# precharge_relays.net
KiCad netlist of a schematic drawn in Altium Designer
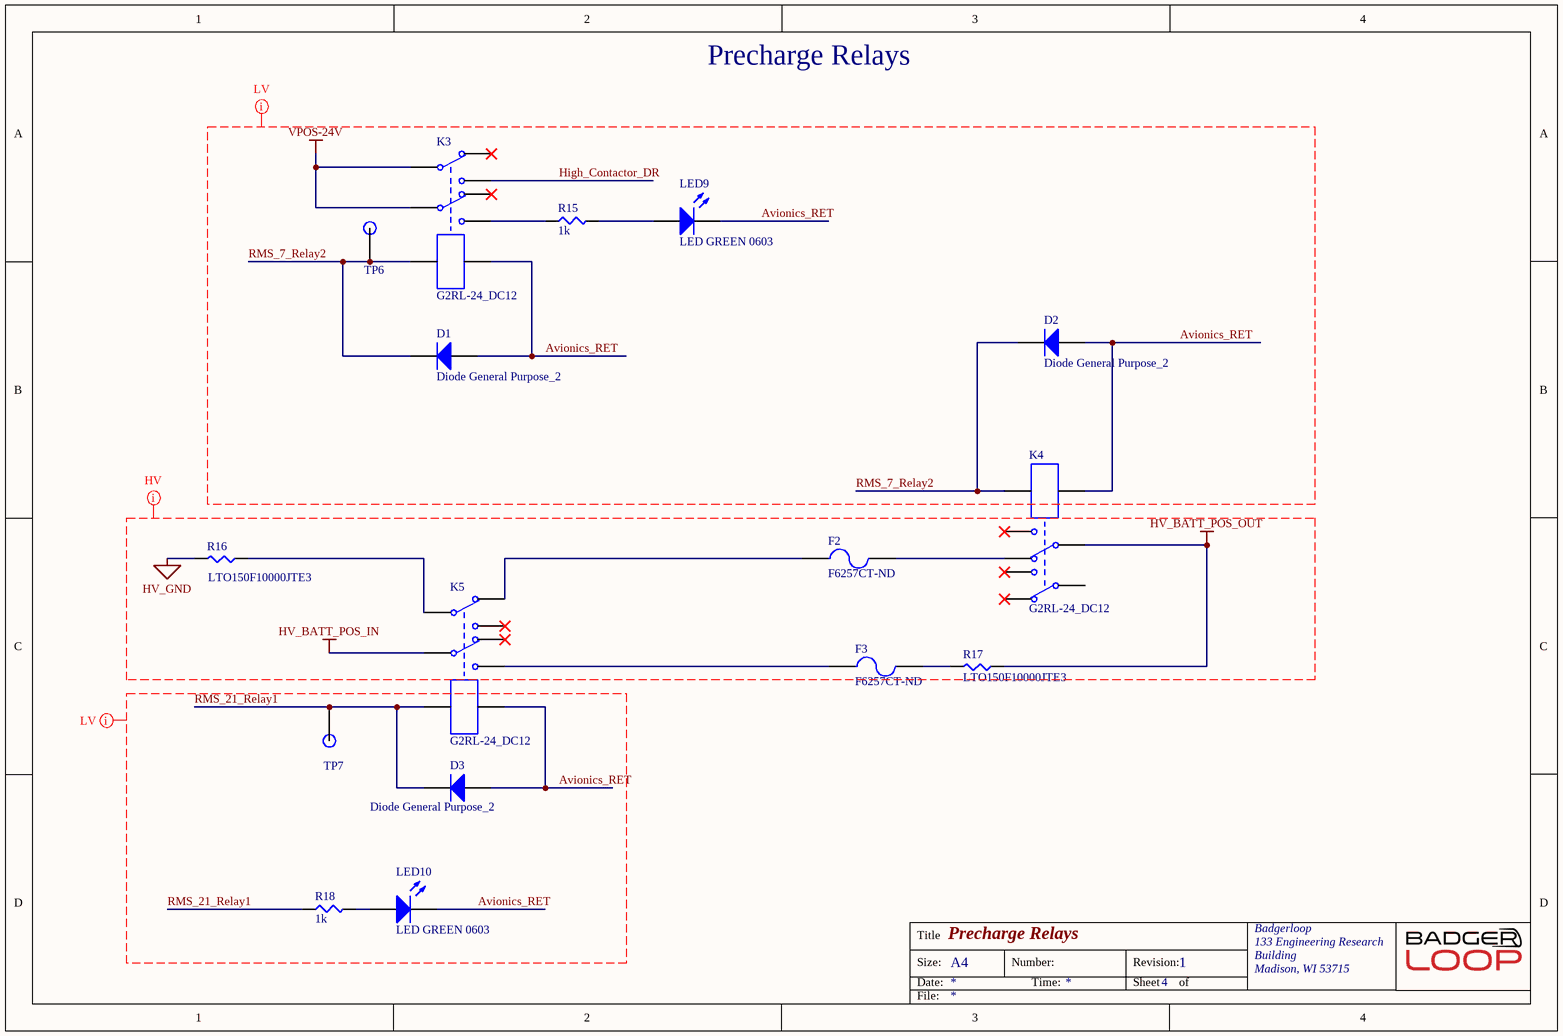
[diagram p0: precharge_relays.SchDoc]

(export (version "E")
  (design (tool "Eeschema 10.0.6"))
  (components
    (comp (ref "D1")
      (value "Diode General Purpose_2")
      (footprint "SODFL250X110-2N")
      (description "DIODE GEN PURP 20V 350MA SOD323")
      (fields (field (name "MANUFACTURER") "Diodes Incorporated"))
      (libsource (lib "misc") (part "Diode General Purpose_2"))
    )
    (comp (ref "D2")
      (value "Diode General Purpose_2")
      (footprint "SODFL250X110-2N")
      (description "DIODE GEN PURP 20V 350MA SOD323")
      (fields (field (name "MANUFACTURER") "Diodes Incorporated"))
      (libsource (lib "misc") (part "Diode General Purpose_2"))
    )
    (comp (ref "D3")
      (value "Diode General Purpose_2")
      (footprint "SODFL250X110-2N")
      (description "DIODE GEN PURP 20V 350MA SOD323")
      (fields (field (name "MANUFACTURER") "Diodes Incorporated"))
      (libsource (lib "misc") (part "Diode General Purpose_2"))
    )
    (comp (ref "F2")
      (value "F6257CT-ND")
      (footprint "FUSE BOARD MNT 500MA 350VAC/VDC")
      (description "FUSE BOARD MNT 500MA 350VAC/VDC")
      (fields (field (name "MANUFACTURER") "Littelfuse"))
      (libsource (lib "misc") (part "F6257CT-ND"))
    )
    (comp (ref "F3")
      (value "F6257CT-ND")
      (footprint "FUSE BOARD MNT 500MA 350VAC/VDC")
      (description "FUSE BOARD MNT 500MA 350VAC/VDC")
      (fields (field (name "MANUFACTURER") "Littelfuse"))
      (libsource (lib "misc") (part "F6257CT-ND"))
    )
    (comp (ref "K3")
      (value "G2RL-24_DC12")
      (footprint "G2RL")
      (description "RELAY GEN PURPOSE DPDT 8A 12V")
      (fields (field (name "MANUFACTURER") "Omron Electronics"))
      (libsource (lib "misc") (part "G2RL-24_DC12"))
    )
    (comp (ref "K4")
      (value "G2RL-24_DC12")
      (footprint "G2RL")
      (description "RELAY GEN PURPOSE DPDT 8A 12V")
      (fields (field (name "MANUFACTURER") "Omron Electronics"))
      (libsource (lib "misc") (part "G2RL-24_DC12"))
    )
    (comp (ref "K5")
      (value "G2RL-24_DC12")
      (footprint "G2RL")
      (description "RELAY GEN PURPOSE DPDT 8A 12V")
      (fields (field (name "MANUFACTURER") "Omron Electronics"))
      (libsource (lib "misc") (part "G2RL-24_DC12"))
    )
    (comp (ref "LED9")
      (value "LED GREEN 0603")
      (footprint "LED 0603 GREEN")
      (fields (field (name "MANUFACTURER") "Lite-On Inc."))
      (libsource (lib "misc") (part "LED GREEN 0603"))
    )
    (comp (ref "LED10")
      (value "LED GREEN 0603")
      (footprint "LED 0603 GREEN")
      (fields (field (name "MANUFACTURER") "Lite-On Inc."))
      (libsource (lib "misc") (part "LED GREEN 0603"))
    )
    (comp (ref "R15")
      (value "1k")
      (footprint "SMD-0805-RES")
      (description "RES SMD 1K OHM 1% 1/8W 0805")
      (fields
        (field (name "PART NUMBER") "ERJ-6ENF1001V")
        (field (name "DIGI-KEY PART NUMBER") "P1.00KCCT-ND")
      )
      (libsource (lib "resistors") (part "ERJ-6ENF1001V"))
    )
    (comp (ref "R16")
      (value "LTO150F10000JTE3")
      (footprint "TO-247-2")
      (description "RES 1K OHM 5% 150W TO247-2")
      (fields (field (name "MANUFACTURER") "Vishay Sfernice"))
      (libsource (lib "resistors") (part "LTO150F10000JTE3"))
    )
    (comp (ref "R17")
      (value "LTO150F10000JTE3")
      (footprint "TO-247-2")
      (description "RES 1K OHM 5% 150W TO247-2")
      (fields (field (name "MANUFACTURER") "Vishay Sfernice"))
      (libsource (lib "resistors") (part "LTO150F10000JTE3"))
    )
    (comp (ref "R18")
      (value "1k")
      (footprint "SMD-0805-RES")
      (description "RES SMD 1K OHM 1% 1/8W 0805")
      (fields
        (field (name "PART NUMBER") "ERJ-6ENF1001V")
        (field (name "DIGI-KEY PART NUMBER") "P1.00KCCT-ND")
      )
      (libsource (lib "resistors") (part "ERJ-6ENF1001V"))
    )
    (comp (ref "TP6")
      (value "TP")
      (footprint "Test Point")
      (description "SMD TEST POINT")
      (libsource (lib "misc") (part "TP"))
    )
    (comp (ref "TP7")
      (value "TP")
      (footprint "Test Point")
      (description "SMD TEST POINT")
      (libsource (lib "misc") (part "TP"))
    )
  )
  (nets
    (net (code "1") (name "/Avionics_RET") (class "Default")
      (node (ref "D1") (pin "1") (pinfunction "A_1") (pintype "passive"))
      (node (ref "D2") (pin "1") (pinfunction "A_1") (pintype "passive"))
      (node (ref "D3") (pin "1") (pinfunction "A_1") (pintype "passive"))
      (node (ref "K3") (pin "8") (pinfunction "8_8") (pintype "passive"))
      (node (ref "K4") (pin "1") (pinfunction "1_1") (pintype "passive"))
      (node (ref "K5") (pin "8") (pinfunction "8_8") (pintype "passive"))
      (node (ref "LED10") (pin "2") (pinfunction "K_2") (pintype "passive"))
      (node (ref "LED9") (pin "2") (pinfunction "K_2") (pintype "passive"))
    )
    (net (code "2") (name "/High_Contactor_DR") (class "Default")
      (node (ref "K3") (pin "4") (pinfunction "4_4") (pintype "passive"))
    )
    (net (code "3") (name "/RMS_7_Relay2") (class "Default")
      (node (ref "D1") (pin "2") (pinfunction "K_2") (pintype "passive"))
      (node (ref "D2") (pin "2") (pinfunction "K_2") (pintype "passive"))
      (node (ref "K3") (pin "1") (pinfunction "1_1") (pintype "passive"))
      (node (ref "K4") (pin "8") (pinfunction "8_8") (pintype "passive"))
      (node (ref "TP6") (pin "1") (pinfunction "1_1") (pintype "passive"))
    )
    (net (code "4") (name "/RMS_21_Relay1") (class "Default")
      (node (ref "D3") (pin "2") (pinfunction "K_2") (pintype "passive"))
      (node (ref "K5") (pin "1") (pinfunction "1_1") (pintype "passive"))
      (node (ref "R18") (pin "1") (pinfunction "1_1") (pintype "passive"))
      (node (ref "TP7") (pin "1") (pinfunction "1_1") (pintype "passive"))
    )
    (net (code "5") (name "HV_BATT_POS_IN") (class "Default")
      (node (ref "K5") (pin "6") (pinfunction "6_6") (pintype "passive"))
    )
    (net (code "6") (name "HV_BATT_POS_OUT") (class "Default")
      (node (ref "K4") (pin "6") (pinfunction "6_6") (pintype "passive"))
      (node (ref "R17") (pin "1") (pinfunction "1_1") (pintype "passive"))
    )
    (net (code "7") (name "HV_GND") (class "Default")
      (node (ref "R16") (pin "2") (pinfunction "2_2") (pintype "passive"))
    )
    (net (code "8") (name "Net-(F2-Pad1)") (class "Default")
      (node (ref "F2") (pin "1") (pinfunction "1_1") (pintype "passive"))
      (node (ref "K5") (pin "2") (pinfunction "2_2") (pintype "passive"))
    )
    (net (code "9") (name "Net-(F2-Pad2)") (class "Default")
      (node (ref "F2") (pin "2") (pinfunction "2_2") (pintype "passive"))
      (node (ref "K4") (pin "7") (pinfunction "7_7") (pintype "passive"))
    )
    (net (code "10") (name "Net-(F3-Pad1)") (class "Default")
      (node (ref "F3") (pin "1") (pinfunction "1_1") (pintype "passive"))
      (node (ref "K5") (pin "5") (pinfunction "5_5") (pintype "passive"))
    )
    (net (code "11") (name "Net-(F3-Pad2)") (class "Default")
      (node (ref "F3") (pin "2") (pinfunction "2_2") (pintype "passive"))
      (node (ref "R17") (pin "2") (pinfunction "2_2") (pintype "passive"))
    )
    (net (code "12") (name "Net-(K3-Pad5)") (class "Default")
      (node (ref "K3") (pin "5") (pinfunction "5_5") (pintype "passive"))
      (node (ref "R15") (pin "1") (pinfunction "1_1") (pintype "passive"))
    )
    (net (code "13") (name "Net-(K5-Pad3)") (class "Default")
      (node (ref "K5") (pin "3") (pinfunction "3_3") (pintype "passive"))
      (node (ref "R16") (pin "1") (pinfunction "1_1") (pintype "passive"))
    )
    (net (code "14") (name "Net-(LED9-A)") (class "Default")
      (node (ref "LED9") (pin "1") (pinfunction "A_1") (pintype "passive"))
      (node (ref "R15") (pin "2") (pinfunction "2_2") (pintype "passive"))
    )
    (net (code "15") (name "Net-(LED10-A)") (class "Default")
      (node (ref "LED10") (pin "1") (pinfunction "A_1") (pintype "passive"))
      (node (ref "R18") (pin "2") (pinfunction "2_2") (pintype "passive"))
    )
    (net (code "16") (name "VPOS-24V") (class "Default")
      (node (ref "K3") (pin "3") (pinfunction "3_3") (pintype "passive"))
      (node (ref "K3") (pin "6") (pinfunction "6_6") (pintype "passive"))
    )
    (net (code "17") (name "unconnected-(K3-Pad2)") (class "Default")
      (node (ref "K3") (pin "2") (pinfunction "2_2") (pintype "passive+no_connect"))
    )
    (net (code "18") (name "unconnected-(K3-Pad7)") (class "Default")
      (node (ref "K3") (pin "7") (pinfunction "7_7") (pintype "passive+no_connect"))
    )
    (net (code "19") (name "unconnected-(K4-Pad2)") (class "Default")
      (node (ref "K4") (pin "2") (pinfunction "2_2") (pintype "passive+no_connect"))
    )
    (net (code "20") (name "unconnected-(K4-Pad3)") (class "Default")
      (node (ref "K4") (pin "3") (pinfunction "3_3") (pintype "passive"))
    )
    (net (code "21") (name "unconnected-(K4-Pad4)") (class "Default")
      (node (ref "K4") (pin "4") (pinfunction "4_4") (pintype "passive+no_connect"))
    )
    (net (code "22") (name "unconnected-(K4-Pad5)") (class "Default")
      (node (ref "K4") (pin "5") (pinfunction "5_5") (pintype "passive+no_connect"))
    )
    (net (code "23") (name "unconnected-(K5-Pad4)") (class "Default")
      (node (ref "K5") (pin "4") (pinfunction "4_4") (pintype "passive+no_connect"))
    )
    (net (code "24") (name "unconnected-(K5-Pad7)") (class "Default")
      (node (ref "K5") (pin "7") (pinfunction "7_7") (pintype "passive+no_connect"))
    )
  )
)
